# REF-IN-BLE-NS_4-2_Rigid.net
KiCad netlist of a schematic drawn in EAGLE
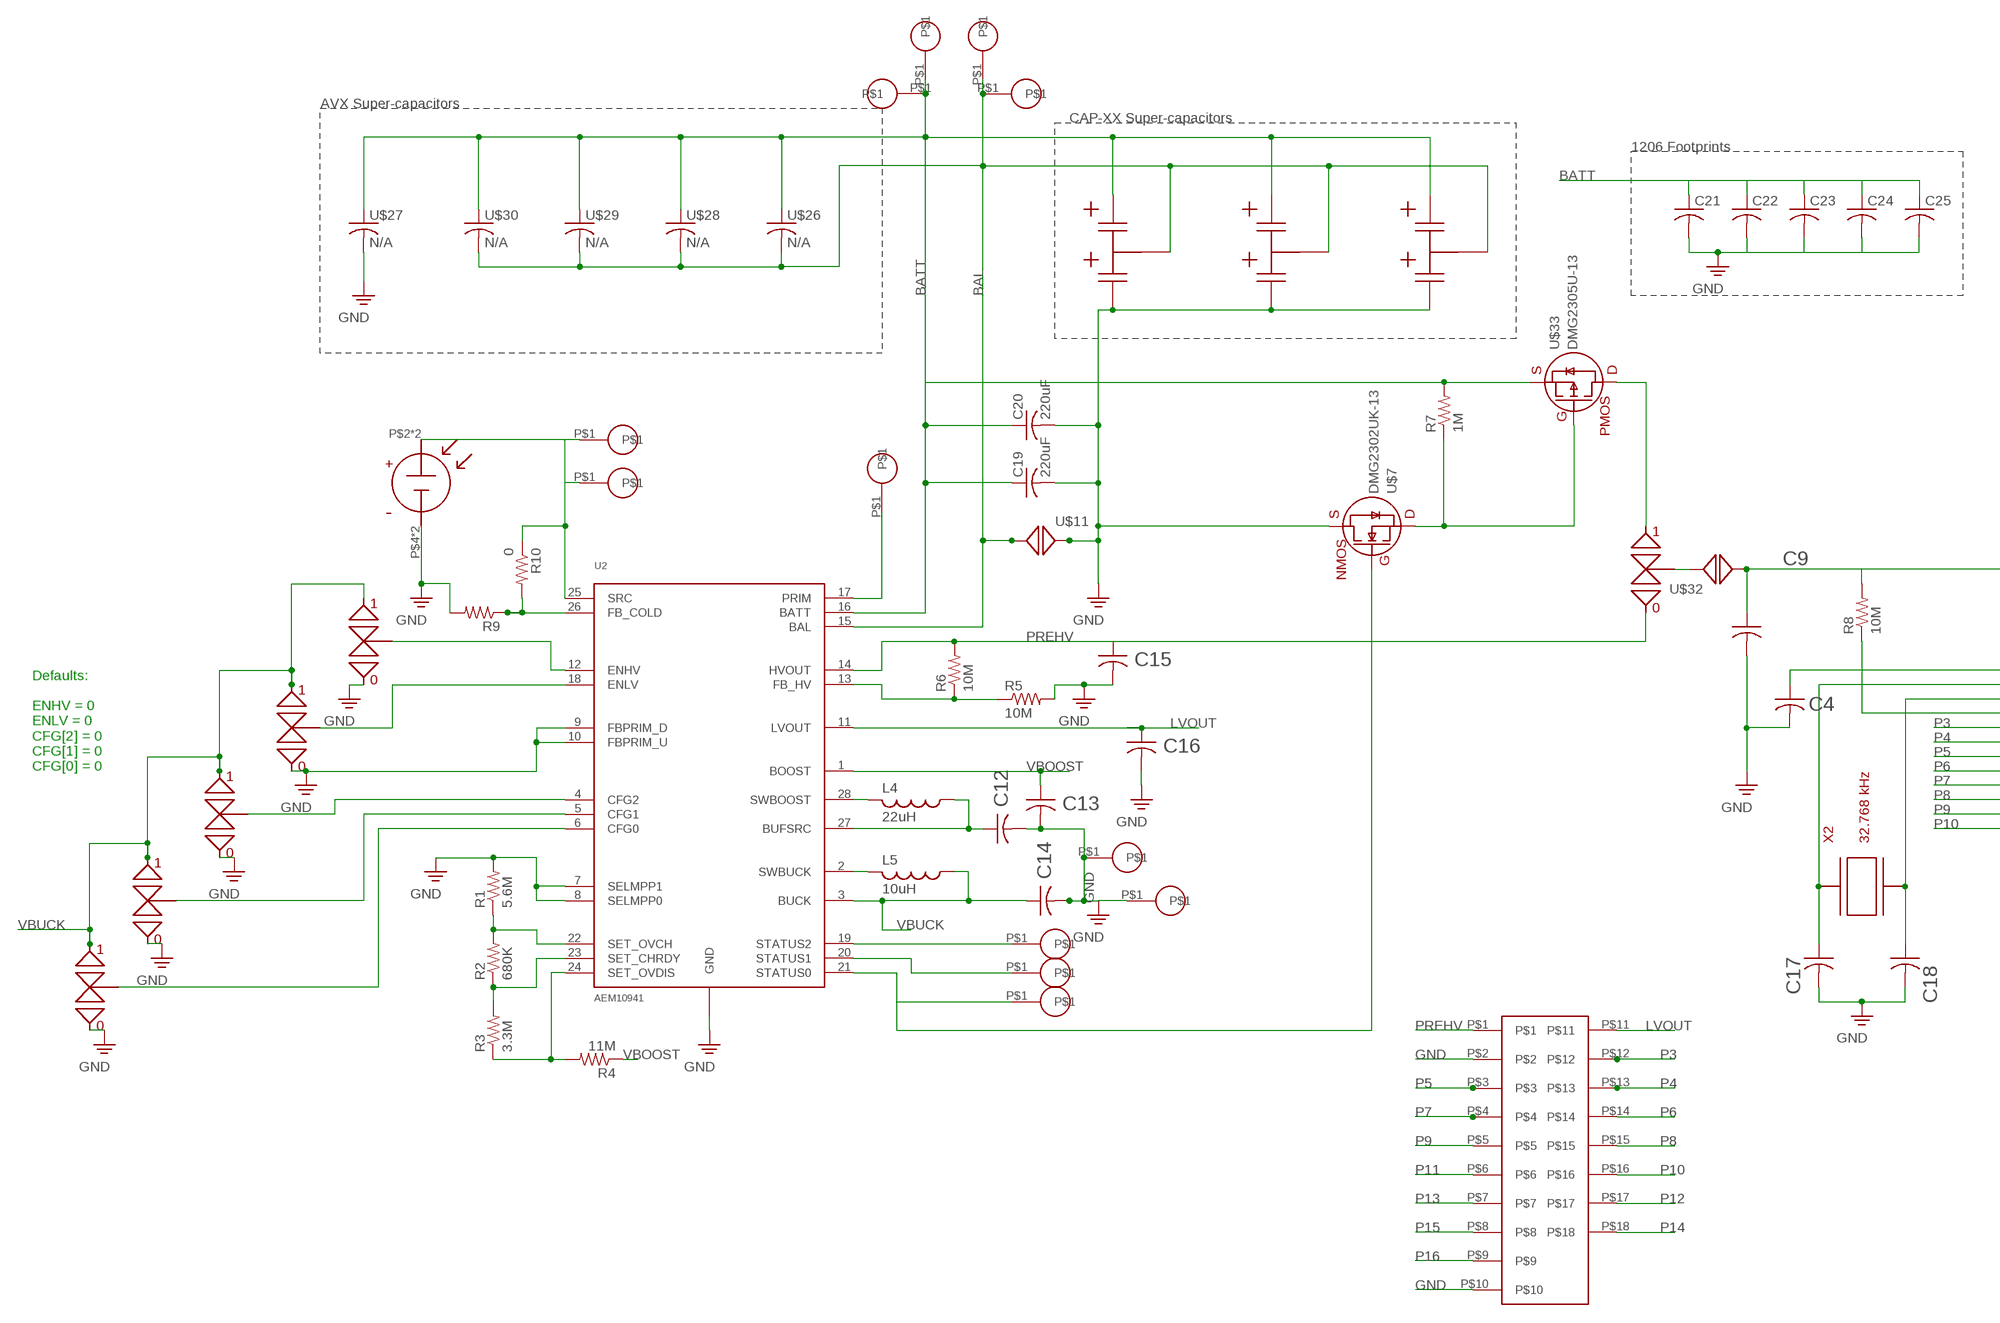
[diagram p0: schematic, sheet 1, part 1 of 2]
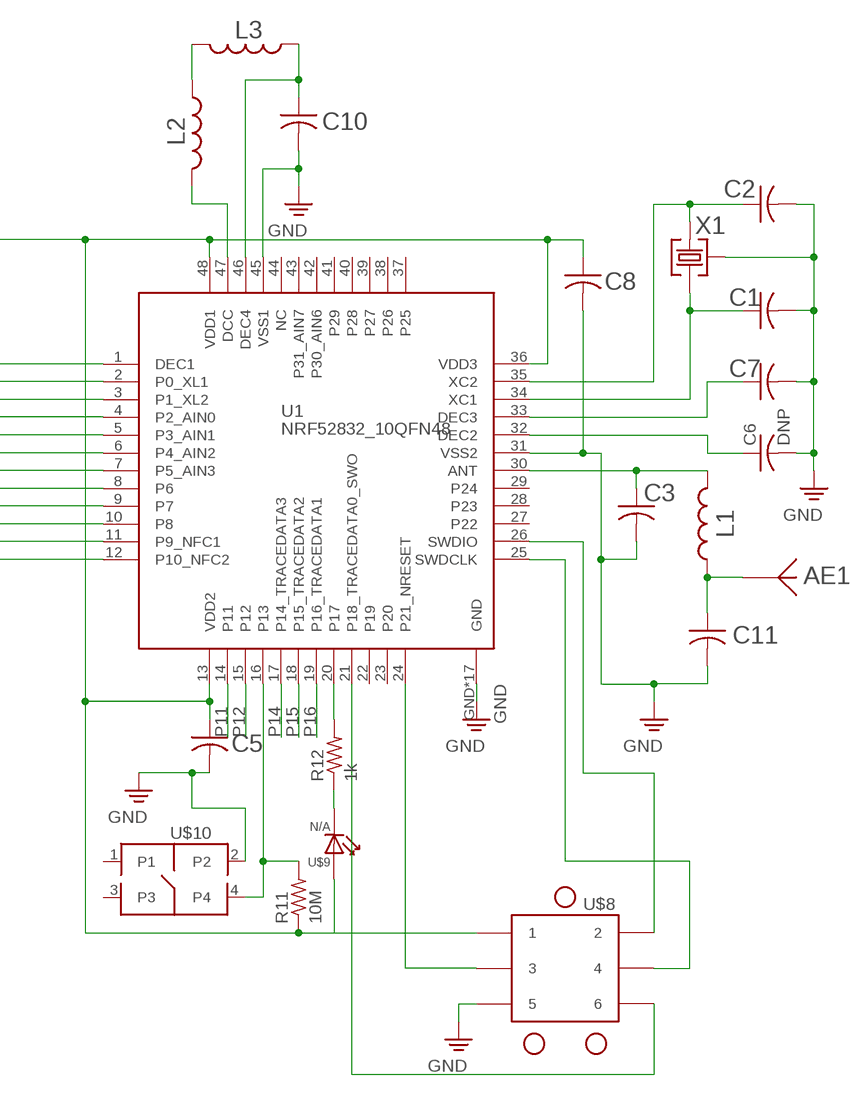
[diagram p1: schematic, sheet 1, part 2 of 2]

(export (version "E")
  (design (tool "Eeschema 10.0.6"))
  (components
    (comp (ref "AE1")
      (value "2.4GHZ_ANTENNAFLIPPED")
      (footprint "eagle-import:BLE_ANTENNA_NORDIC_FLIPPED")
      (libsource (lib "eagle-import") (part "2.4GHZ_ANTENNAFLIPPED"))
    )
    (comp (ref "C1")
      (value "12pF")
      (footprint "eagle-import:C0603")
      (fields (field (name "MFG_PART#") "C0603C120J5GACTU"))
      (libsource (lib "eagle-import") (part "C-USC0603T-12PF"))
    )
    (comp (ref "C2")
      (value "12pF")
      (footprint "eagle-import:C0603")
      (fields (field (name "MFG_PART#") "C0603C120J5GACTU"))
      (libsource (lib "eagle-import") (part "C-USC0603T-12PF"))
    )
    (comp (ref "C3")
      (value "0.8pF")
      (footprint "eagle-import:C0603")
      (fields (field (name "MFG_PART#") "CBR06C808B5GAC "))
      (libsource (lib "eagle-import") (part "C-USC0603T-0.8PF"))
    )
    (comp (ref "C4")
      (value "100nF")
      (footprint "eagle-import:C0603")
      (fields (field (name "MFG_PART#") "CL10B104KB8NNNC"))
      (libsource (lib "eagle-import") (part "C-USC0603T-100NF"))
    )
    (comp (ref "C5")
      (value "100nF")
      (footprint "eagle-import:C0603")
      (fields (field (name "MFG_PART#") "CL10B104KB8NNNC"))
      (libsource (lib "eagle-import") (part "C-USC0603T-100NF"))
    )
    (comp (ref "C6")
      (value "DNP")
      (footprint "eagle-import:C0603")
      (libsource (lib "eagle-import") (part "C-USC0603"))
    )
    (comp (ref "C7")
      (value "100pF")
      (footprint "eagle-import:C0603")
      (fields (field (name "MFG_PART#") "CL10C101JB8NNNC"))
      (libsource (lib "eagle-import") (part "C-USC0603T-100PF"))
    )
    (comp (ref "C8")
      (value "100nF")
      (footprint "eagle-import:C0603")
      (fields (field (name "MFG_PART#") "CL10B104KB8NNNC"))
      (libsource (lib "eagle-import") (part "C-USC0603T-100NF"))
    )
    (comp (ref "C9")
      (value "4.7uF")
      (footprint "eagle-import:C0603")
      (fields (field (name "MFG_PART#") "CL10A475KQ8NNWC "))
      (libsource (lib "eagle-import") (part "C-USC0603T-4.7UF"))
    )
    (comp (ref "C10")
      (value "1uF")
      (footprint "eagle-import:C0603")
      (fields (field (name "MFG_PART#") "CL10A105KP8NNNC ") (field (name "PERCENTAGE") "10%"))
      (libsource (lib "eagle-import") (part "C-USC0603T-1UF"))
    )
    (comp (ref "C11")
      (value "DNP")
      (footprint "eagle-import:C0603")
      (libsource (lib "eagle-import") (part "C-USC0603"))
    )
    (comp (ref "C12")
      (value "10uF")
      (footprint "eagle-import:C0603")
      (fields (field (name "MFG_PART#") "GRM188R61E106MA73D"))
      (libsource (lib "eagle-import") (part "C-USC0603T-10UF"))
    )
    (comp (ref "C13")
      (value "22uF")
      (footprint "eagle-import:C0603")
      (fields (field (name "MFG_PART#") "GRM188R61A226ME15D"))
      (libsource (lib "eagle-import") (part "C-USC0603T-22UF"))
    )
    (comp (ref "C14")
      (value "10uF")
      (footprint "eagle-import:C0603")
      (fields (field (name "MFG_PART#") "GRM188R61E106MA73D"))
      (libsource (lib "eagle-import") (part "C-USC0603T-10UF"))
    )
    (comp (ref "C15")
      (value "10uF")
      (footprint "eagle-import:C0603")
      (fields (field (name "MFG_PART#") "GRM188R61E106MA73D"))
      (libsource (lib "eagle-import") (part "C-USC0603T-10UF"))
    )
    (comp (ref "C16")
      (value "10uF")
      (footprint "eagle-import:C0603")
      (fields (field (name "MFG_PART#") "GRM188R61E106MA73D"))
      (libsource (lib "eagle-import") (part "C-USC0603T-10UF"))
    )
    (comp (ref "C17")
      (value "12p")
      (footprint "eagle-import:C0603")
      (fields (field (name "MFG_PART#") "C0603C120J5GACTU"))
      (libsource (lib "eagle-import") (part "C-USC0603T-12PF"))
    )
    (comp (ref "C18")
      (value "12p")
      (footprint "eagle-import:C0603")
      (fields (field (name "MFG_PART#") "C0603C120J5GACTU"))
      (libsource (lib "eagle-import") (part "C-USC0603T-12PF"))
    )
    (comp (ref "C19")
      (value "220uF")
      (footprint "eagle-import:C1206")
      (fields (field (name "MFG_PART#") "GRM31CC80G227ME11L"))
      (libsource (lib "eagle-import") (part "C-USC1206T-220UF"))
    )
    (comp (ref "C20")
      (value "220uF")
      (footprint "eagle-import:C1206")
      (fields (field (name "MFG_PART#") "GRM31CC80G227ME11L"))
      (libsource (lib "eagle-import") (part "C-USC1206T-220UF"))
    )
    (comp (ref "C21")
      (value "C-USC1206")
      (footprint "eagle-import:C1206")
      (libsource (lib "eagle-import") (part "C-USC1206"))
    )
    (comp (ref "C22")
      (value "C-USC1206")
      (footprint "eagle-import:C1206")
      (libsource (lib "eagle-import") (part "C-USC1206"))
    )
    (comp (ref "C23")
      (value "C-USC1206")
      (footprint "eagle-import:C1206")
      (libsource (lib "eagle-import") (part "C-USC1206"))
    )
    (comp (ref "C24")
      (value "C-USC1206")
      (footprint "eagle-import:C1206")
      (libsource (lib "eagle-import") (part "C-USC1206"))
    )
    (comp (ref "C25")
      (value "C-USC1206")
      (footprint "eagle-import:C1206")
      (libsource (lib "eagle-import") (part "C-USC1206"))
    )
    (comp (ref "L1")
      (value "3.9nH")
      (footprint "eagle-import:L0603")
      (fields (field (name "MFG_PART#") "L-14C3N9SV4T "))
      (libsource (lib "eagle-import") (part "L0603V-3.9NH"))
    )
    (comp (ref "L2")
      (value "10uH")
      (footprint "eagle-import:L0603")
      (fields (field (name "MFG_PART#") "LBR2012T100M"))
      (libsource (lib "eagle-import") (part "L0603V-10UH"))
    )
    (comp (ref "L3")
      (value "15nH")
      (footprint "eagle-import:L0603")
      (fields (field (name "MFG_PART#") "L-14C15NJV4T"))
      (libsource (lib "eagle-import") (part "L0603V-15NH"))
    )
    (comp (ref "L4")
      (value "22uH")
      (footprint "eagle-import:L1206")
      (libsource (lib "eagle-import") (part "L1206"))
    )
    (comp (ref "L5")
      (value "10uH")
      (footprint "eagle-import:L0603")
      (fields (field (name "MFG_PART#") "LBR2012T100M"))
      (libsource (lib "eagle-import") (part "L0603V-10UH"))
    )
    (comp (ref "R1")
      (value "5.6M")
      (footprint "eagle-import:R0603")
      (libsource (lib "eagle-import") (part "R-US_R0603"))
    )
    (comp (ref "R2")
      (value "680K")
      (footprint "eagle-import:R0603")
      (libsource (lib "eagle-import") (part "R-US_R0603"))
    )
    (comp (ref "R3")
      (value "3.3M")
      (footprint "eagle-import:R0603")
      (libsource (lib "eagle-import") (part "R-US_R0603"))
    )
    (comp (ref "R4")
      (value "11M")
      (footprint "eagle-import:R0603")
      (libsource (lib "eagle-import") (part "R-US_R0603"))
    )
    (comp (ref "R5")
      (value "10M")
      (footprint "eagle-import:R0603")
      (libsource (lib "eagle-import") (part "R-US_R0603"))
    )
    (comp (ref "R6")
      (value "10M")
      (footprint "eagle-import:R0603")
      (libsource (lib "eagle-import") (part "R-US_R0603"))
    )
    (comp (ref "R7")
      (value "1M")
      (footprint "eagle-import:R0603")
      (libsource (lib "eagle-import") (part "R-US_R0603"))
    )
    (comp (ref "R8")
      (value "10M")
      (footprint "eagle-import:R0603")
      (libsource (lib "eagle-import") (part "R-US_R0603"))
    )
    (comp (ref "R9")
      (value "R-US_R0603")
      (footprint "eagle-import:R0603")
      (libsource (lib "eagle-import") (part "R-US_R0603"))
    )
    (comp (ref "R10")
      (value "0")
      (footprint "eagle-import:R0603")
      (libsource (lib "eagle-import") (part "R-US_R0603"))
    )
    (comp (ref "R11")
      (value "10M")
      (footprint "eagle-import:R0603")
      (libsource (lib "eagle-import") (part "R-US_R0603"))
    )
    (comp (ref "R12")
      (value "1k")
      (footprint "eagle-import:R0603")
      (libsource (lib "eagle-import") (part "R-US_R0603"))
    )
    (comp (ref "U$2")
      (value "N/A")
      (footprint "eagle-import:DOUBLE_SOLDER_BRIDGE_0_CLOSED")
      (libsource (lib "eagle-import") (part "DOUBLE_SOLDER_BRIDGE0_CLOSED"))
    )
    (comp (ref "U$3")
      (value "N/A")
      (footprint "eagle-import:DOUBLE_SOLDER_BRIDGE_0_CLOSED")
      (libsource (lib "eagle-import") (part "DOUBLE_SOLDER_BRIDGE0_CLOSED"))
    )
    (comp (ref "U$4")
      (value "N/A")
      (footprint "eagle-import:DOUBLE_SOLDER_BRIDGE_0_CLOSED")
      (libsource (lib "eagle-import") (part "DOUBLE_SOLDER_BRIDGE0_CLOSED"))
    )
    (comp (ref "U$5")
      (value "N/A")
      (footprint "eagle-import:DOUBLE_SOLDER_BRIDGE_0_CLOSED")
      (libsource (lib "eagle-import") (part "DOUBLE_SOLDER_BRIDGE0_CLOSED"))
    )
    (comp (ref "U$6")
      (value "N/A")
      (footprint "eagle-import:DOUBLE_SOLDER_BRIDGE_0_CLOSED")
      (libsource (lib "eagle-import") (part "DOUBLE_SOLDER_BRIDGE0_CLOSED"))
    )
    (comp (ref "U$7")
      (value "DMG2302UK-13")
      (footprint "eagle-import:SOT-23-3-DIODESINC")
      (libsource (lib "eagle-import") (part "DMG2302UK-13"))
    )
    (comp (ref "U$8")
      (value "N/A")
      (footprint "eagle-import:TC2030-IDC")
      (libsource (lib "eagle-import") (part "TC2030-IDC"))
    )
    (comp (ref "U$9")
      (value "N/A")
      (footprint "eagle-import:APT1608LZGCK")
      (fields (field (name "MFG_PART#") "APT1608LZGCK"))
      (libsource (lib "eagle-import") (part "APT1608LZGCK"))
    )
    (comp (ref "U$10")
      (value "MJTP1140")
      (footprint "eagle-import:MJTP1140A")
      (fields (field (name "MFG_PART#") "TL3315NF100Q "))
      (libsource (lib "eagle-import") (part "MJTP1140"))
    )
    (comp (ref "U$11")
      (value "SOLDER_BRIGDECLOSED")
      (footprint "eagle-import:SOLDER_BRIDGE_CLOSED")
      (libsource (lib "eagle-import") (part "SOLDER_BRIGDECLOSED"))
    )
    (comp (ref "U$12")
      (value "N/A")
      (footprint "eagle-import:1MM_PAD")
      (libsource (lib "eagle-import") (part "1MM_PAD"))
    )
    (comp (ref "U$13")
      (value "N/A")
      (footprint "eagle-import:1MM_PAD")
      (libsource (lib "eagle-import") (part "1MM_PAD"))
    )
    (comp (ref "U$14")
      (value "N/A")
      (footprint "eagle-import:1MM_PAD")
      (libsource (lib "eagle-import") (part "1MM_PAD"))
    )
    (comp (ref "U$15")
      (value "N/A")
      (footprint "eagle-import:1MM_PAD")
      (libsource (lib "eagle-import") (part "1MM_PAD"))
    )
    (comp (ref "U$16")
      (value "SOLAR_CELL_LL200-2.4-37")
      (footprint "eagle-import:SOLAR_CELL_37X54MM")
      (libsource (lib "eagle-import") (part "SOLAR_CELL_LL200-2.4-37"))
    )
    (comp (ref "U$17")
      (value "N/A")
      (footprint "eagle-import:1MM_PAD")
      (libsource (lib "eagle-import") (part "1MM_PAD"))
    )
    (comp (ref "U$18")
      (value "N/A")
      (footprint "eagle-import:1MM_PAD")
      (libsource (lib "eagle-import") (part "1MM_PAD"))
    )
    (comp (ref "U$19")
      (value "N/A")
      (footprint "eagle-import:1MM_PAD")
      (libsource (lib "eagle-import") (part "1MM_PAD"))
    )
    (comp (ref "U$20")
      (value "18PIN_CONN")
      (footprint "eagle-import:20PIN_CONN")
      (libsource (lib "eagle-import") (part "18PIN_CONN"))
    )
    (comp (ref "U$23")
      (value "N/A")
      (footprint "eagle-import:CAP-XX_A-TYPE")
      (libsource (lib "eagle-import") (part "CAP-XX_A-TYPE"))
    )
    (comp (ref "U$24")
      (value "N/A")
      (footprint "eagle-import:CAP-XX_S-TYPE")
      (libsource (lib "eagle-import") (part "CAP-XX_S-TYPE"))
    )
    (comp (ref "U$25")
      (value "N/A")
      (footprint "eagle-import:CAP-XX_W-TYPE")
      (libsource (lib "eagle-import") (part "CAP-XX_W-TYPE"))
    )
    (comp (ref "U$26")
      (value "N/A")
      (footprint "eagle-import:BZ01_L-TYPE")
      (libsource (lib "eagle-import") (part "BZ01_L-TYPE"))
    )
    (comp (ref "U$27")
      (value "N/A")
      (footprint "eagle-import:BZ059_N-TYPE")
      (libsource (lib "eagle-import") (part "BZ059_N-TYPE"))
    )
    (comp (ref "U$28")
      (value "N/A")
      (footprint "eagle-import:BZ01_S-TYPE")
      (libsource (lib "eagle-import") (part "BZ01_S-TYPE"))
    )
    (comp (ref "U$29")
      (value "N/A")
      (footprint "eagle-import:BZ05_S-TYPE")
      (libsource (lib "eagle-import") (part "BZ05_S-TYPE"))
    )
    (comp (ref "U$30")
      (value "N/A")
      (footprint "eagle-import:BZ09_S-TYPE")
      (libsource (lib "eagle-import") (part "BZ09_S-TYPE"))
    )
    (comp (ref "U$31")
      (value "DOUBLE_SOLDER_BRIDGE1_CLOSED")
      (footprint "eagle-import:DOUBLE_SOLDER_BRIDGE_1_CLOSED")
      (libsource (lib "eagle-import") (part "DOUBLE_SOLDER_BRIDGE1_CLOSED"))
    )
    (comp (ref "U$32")
      (value "SOLDER_BRIGDECLOSED")
      (footprint "eagle-import:SOLDER_BRIDGE_CLOSED")
      (libsource (lib "eagle-import") (part "SOLDER_BRIGDECLOSED"))
    )
    (comp (ref "U$33")
      (value "DMG2305U-13")
      (footprint "eagle-import:SOT-23-3-DIODESINC")
      (libsource (lib "eagle-import") (part "DMG2305U-13"))
    )
    (comp (ref "U$35")
      (value "N/A")
      (footprint "eagle-import:1MM_PAD")
      (libsource (lib "eagle-import") (part "1MM_PAD"))
    )
    (comp (ref "U$36")
      (value "N/A")
      (footprint "eagle-import:1MM_PAD")
      (libsource (lib "eagle-import") (part "1MM_PAD"))
    )
    (comp (ref "U$39")
      (value "N/A")
      (footprint "eagle-import:1MM_PAD")
      (libsource (lib "eagle-import") (part "1MM_PAD"))
    )
    (comp (ref "U$40")
      (value "N/A")
      (footprint "eagle-import:1MM_PAD")
      (libsource (lib "eagle-import") (part "1MM_PAD"))
    )
    (comp (ref "U$41")
      (value "N/A")
      (footprint "eagle-import:1MM_PAD")
      (libsource (lib "eagle-import") (part "1MM_PAD"))
    )
    (comp (ref "U1")
      (value "NRF52832_10QFN48")
      (footprint "eagle-import:NRF52832_10")
      (fields (field (name "MFG_PART#") "NRF52832-QFAA-R"))
      (libsource (lib "eagle-import") (part "NRF52832_10QFN48"))
    )
    (comp (ref "U2")
      (value "AEM10941")
      (footprint "eagle-import:QFN28_5X5_05PITCH")
      (fields (field (name "MFG_PART#") "AEM10941-QFN "))
      (libsource (lib "eagle-import") (part "AEM10941"))
    )
    (comp (ref "X1")
      (value "32 MHz")
      (footprint "eagle-import:FA-128-EPSON")
      (fields (field (name "MFG_PART#") "FA-128 32.0000MF10Z-AJ3"))
      (libsource (lib "eagle-import") (part "FA-128-32MHZMF10Z-AJ5"))
    )
    (comp (ref "X2")
      (value "32.768 kHz")
      (footprint "eagle-import:FC-135")
      (fields (field (name "MFG_PART#") "FC-135 32.7680KA-AC"))
      (libsource (lib "eagle-import") (part "FC-135_32.7680KA-AC"))
    )
  )
  (nets
    (net (code "1") (name "/BAL") (class "Default")
      (node (ref "U$11") (pin "P$1") (pinfunction "P1_P$1") (pintype "bidirectional"))
      (node (ref "U$19") (pin "P$1") (pinfunction "P$1_P$1") (pintype "bidirectional"))
      (node (ref "U$23") (pin "P$1") (pinfunction "BAL_P$1") (pintype "bidirectional"))
      (node (ref "U$24") (pin "P$1") (pinfunction "BAL_P$1") (pintype "bidirectional"))
      (node (ref "U$25") (pin "P$1") (pinfunction "BAL_P$1") (pintype "bidirectional"))
      (node (ref "U$26") (pin "P$3") (pinfunction "2_P$3") (pintype "passive"))
      (node (ref "U$26") (pin "P$4") (pinfunction "2_P$4") (pintype "passive"))
      (node (ref "U$28") (pin "P$3") (pinfunction "2_P$3") (pintype "passive"))
      (node (ref "U$29") (pin "P$3") (pinfunction "2_P$3") (pintype "passive"))
      (node (ref "U$30") (pin "P$3") (pinfunction "2_P$3") (pintype "passive"))
      (node (ref "U$41") (pin "P$1") (pinfunction "P$1_P$1") (pintype "bidirectional"))
      (node (ref "U2") (pin "15") (pinfunction "BAL_15") (pintype "bidirectional"))
    )
    (net (code "2") (name "/BATT") (class "Default")
      (node (ref "C19") (pin "1") (pinfunction "1_1") (pintype "passive"))
      (node (ref "C20") (pin "1") (pinfunction "1_1") (pintype "passive"))
      (node (ref "C21") (pin "1") (pinfunction "1_1") (pintype "passive"))
      (node (ref "C22") (pin "1") (pinfunction "1_1") (pintype "passive"))
      (node (ref "C23") (pin "1") (pinfunction "1_1") (pintype "passive"))
      (node (ref "C24") (pin "1") (pinfunction "1_1") (pintype "passive"))
      (node (ref "C25") (pin "1") (pinfunction "1_1") (pintype "passive"))
      (node (ref "R7") (pin "2") (pinfunction "2_2") (pintype "passive"))
      (node (ref "U$18") (pin "P$1") (pinfunction "P$1_P$1") (pintype "bidirectional"))
      (node (ref "U$23") (pin "P$2") (pinfunction "+_P$2") (pintype "bidirectional"))
      (node (ref "U$24") (pin "P$2") (pinfunction "+_P$2") (pintype "bidirectional"))
      (node (ref "U$25") (pin "P$2") (pinfunction "+_P$2") (pintype "bidirectional"))
      (node (ref "U$26") (pin "P$1") (pinfunction "1_P$1") (pintype "passive"))
      (node (ref "U$26") (pin "P$2") (pinfunction "1_P$2") (pintype "passive"))
      (node (ref "U$27") (pin "P$1") (pinfunction "1_P$1") (pintype "passive"))
      (node (ref "U$28") (pin "P$1") (pinfunction "1_P$1") (pintype "passive"))
      (node (ref "U$28") (pin "P$2") (pinfunction "1_P$2") (pintype "passive"))
      (node (ref "U$29") (pin "P$1") (pinfunction "1_P$1") (pintype "passive"))
      (node (ref "U$29") (pin "P$2") (pinfunction "1_P$2") (pintype "passive"))
      (node (ref "U$30") (pin "P$1") (pinfunction "1_P$1") (pintype "passive"))
      (node (ref "U$30") (pin "P$2") (pinfunction "1_P$2") (pintype "passive"))
      (node (ref "U$33") (pin "2") (pinfunction "S_2") (pintype "bidirectional"))
      (node (ref "U$40") (pin "P$1") (pinfunction "P$1_P$1") (pintype "bidirectional"))
      (node (ref "U2") (pin "16") (pinfunction "BATT_16") (pintype "bidirectional"))
    )
    (net (code "3") (name "/LVOUT") (class "Default")
      (node (ref "C16") (pin "1") (pinfunction "1_1") (pintype "passive"))
      (node (ref "U$20") (pin "P$11") (pinfunction "P$11_P$11") (pintype "bidirectional"))
      (node (ref "U2") (pin "11") (pinfunction "LVOUT_11") (pintype "output"))
    )
    (net (code "4") (name "/P3") (class "Default")
      (node (ref "U$20") (pin "P$12") (pinfunction "P$12_P$12") (pintype "bidirectional"))
      (node (ref "U1") (pin "5") (pinfunction "P3_AIN1_5") (pintype "bidirectional"))
    )
    (net (code "5") (name "/P4") (class "Default")
      (node (ref "U$20") (pin "P$13") (pinfunction "P$13_P$13") (pintype "bidirectional"))
      (node (ref "U1") (pin "6") (pinfunction "P4_AIN2_6") (pintype "bidirectional"))
    )
    (net (code "6") (name "/P5") (class "Default")
      (node (ref "U$20") (pin "P$3") (pinfunction "P$3_P$3") (pintype "bidirectional"))
      (node (ref "U1") (pin "7") (pinfunction "P5_AIN3_7") (pintype "bidirectional"))
    )
    (net (code "7") (name "/P6") (class "Default")
      (node (ref "U$20") (pin "P$14") (pinfunction "P$14_P$14") (pintype "bidirectional"))
      (node (ref "U1") (pin "8") (pinfunction "P6_8") (pintype "bidirectional"))
    )
    (net (code "8") (name "/P7") (class "Default")
      (node (ref "U$20") (pin "P$4") (pinfunction "P$4_P$4") (pintype "bidirectional"))
      (node (ref "U1") (pin "9") (pinfunction "P7_9") (pintype "bidirectional"))
    )
    (net (code "9") (name "/P8") (class "Default")
      (node (ref "U$20") (pin "P$15") (pinfunction "P$15_P$15") (pintype "bidirectional"))
      (node (ref "U1") (pin "10") (pinfunction "P8_10") (pintype "bidirectional"))
    )
    (net (code "10") (name "/P9") (class "Default")
      (node (ref "U$20") (pin "P$5") (pinfunction "P$5_P$5") (pintype "bidirectional"))
      (node (ref "U1") (pin "11") (pinfunction "P9_NFC1_11") (pintype "bidirectional"))
    )
    (net (code "11") (name "/P10") (class "Default")
      (node (ref "U$20") (pin "P$16") (pinfunction "P$16_P$16") (pintype "bidirectional"))
      (node (ref "U1") (pin "12") (pinfunction "P10_NFC2_12") (pintype "bidirectional"))
    )
    (net (code "12") (name "/P11") (class "Default")
      (node (ref "U$20") (pin "P$6") (pinfunction "P$6_P$6") (pintype "bidirectional"))
      (node (ref "U1") (pin "14") (pinfunction "P11_14") (pintype "bidirectional"))
    )
    (net (code "13") (name "/P12") (class "Default")
      (node (ref "U$20") (pin "P$17") (pinfunction "P$17_P$17") (pintype "bidirectional"))
      (node (ref "U1") (pin "15") (pinfunction "P12_15") (pintype "bidirectional"))
    )
    (net (code "14") (name "/P13") (class "Default")
      (node (ref "U$20") (pin "P$7") (pinfunction "P$7_P$7") (pintype "bidirectional"))
    )
    (net (code "15") (name "/P14") (class "Default")
      (node (ref "U$20") (pin "P$18") (pinfunction "P$18_P$18") (pintype "bidirectional"))
      (node (ref "U1") (pin "17") (pinfunction "P14_TRACEDATA3_17") (pintype "bidirectional"))
    )
    (net (code "16") (name "/P15") (class "Default")
      (node (ref "U$20") (pin "P$8") (pinfunction "P$8_P$8") (pintype "bidirectional"))
      (node (ref "U1") (pin "18") (pinfunction "P15_TRACEDATA2_18") (pintype "bidirectional"))
    )
    (net (code "17") (name "/P16") (class "Default")
      (node (ref "U$20") (pin "P$9") (pinfunction "P$9_P$9") (pintype "bidirectional"))
      (node (ref "U1") (pin "19") (pinfunction "P16_TRACEDATA1_19") (pintype "bidirectional"))
    )
    (net (code "18") (name "/PREHV") (class "Default")
      (node (ref "C15") (pin "1") (pinfunction "1_1") (pintype "passive"))
      (node (ref "R6") (pin "2") (pinfunction "2_2") (pintype "passive"))
      (node (ref "U$20") (pin "P$1") (pinfunction "P$1_P$1") (pintype "bidirectional"))
      (node (ref "U$31") (pin "IN0") (pinfunction "IN0_IN0") (pintype "bidirectional"))
      (node (ref "U2") (pin "14") (pinfunction "HVOUT_14") (pintype "output"))
    )
    (net (code "19") (name "/VBOOST") (class "Default")
      (node (ref "C13") (pin "1") (pinfunction "1_1") (pintype "passive"))
      (node (ref "R4") (pin "1") (pinfunction "1_1") (pintype "passive"))
      (node (ref "U2") (pin "1") (pinfunction "BOOST_1") (pintype "bidirectional"))
    )
    (net (code "20") (name "/VBUCK") (class "Default")
      (node (ref "C14") (pin "1") (pinfunction "1_1") (pintype "passive"))
      (node (ref "L5") (pin "1") (pinfunction "1_1") (pintype "passive"))
      (node (ref "U$2") (pin "IN1") (pinfunction "IN1_IN1") (pintype "bidirectional"))
      (node (ref "U$3") (pin "IN1") (pinfunction "IN1_IN1") (pintype "bidirectional"))
      (node (ref "U$4") (pin "IN1") (pinfunction "IN1_IN1") (pintype "bidirectional"))
      (node (ref "U$5") (pin "IN1") (pinfunction "IN1_IN1") (pintype "bidirectional"))
      (node (ref "U$6") (pin "IN1") (pinfunction "IN1_IN1") (pintype "bidirectional"))
      (node (ref "U2") (pin "3") (pinfunction "BUCK_3") (pintype "bidirectional"))
    )
    (net (code "21") (name "GND") (class "Default")
      (node (ref "C1") (pin "2") (pinfunction "2_2") (pintype "passive"))
      (node (ref "C10") (pin "2") (pinfunction "2_2") (pintype "passive"))
      (node (ref "C11") (pin "2") (pinfunction "2_2") (pintype "passive"))
      (node (ref "C12") (pin "2") (pinfunction "2_2") (pintype "passive"))
      (node (ref "C13") (pin "2") (pinfunction "2_2") (pintype "passive"))
      (node (ref "C14") (pin "2") (pinfunction "2_2") (pintype "passive"))
      (node (ref "C15") (pin "2") (pinfunction "2_2") (pintype "passive"))
      (node (ref "C16") (pin "2") (pinfunction "2_2") (pintype "passive"))
      (node (ref "C17") (pin "2") (pinfunction "2_2") (pintype "passive"))
      (node (ref "C18") (pin "2") (pinfunction "2_2") (pintype "passive"))
      (node (ref "C19") (pin "2") (pinfunction "2_2") (pintype "passive"))
      (node (ref "C2") (pin "2") (pinfunction "2_2") (pintype "passive"))
      (node (ref "C20") (pin "2") (pinfunction "2_2") (pintype "passive"))
      (node (ref "C21") (pin "2") (pinfunction "2_2") (pintype "passive"))
      (node (ref "C22") (pin "2") (pinfunction "2_2") (pintype "passive"))
      (node (ref "C23") (pin "2") (pinfunction "2_2") (pintype "passive"))
      (node (ref "C24") (pin "2") (pinfunction "2_2") (pintype "passive"))
      (node (ref "C25") (pin "2") (pinfunction "2_2") (pintype "passive"))
      (node (ref "C3") (pin "2") (pinfunction "2_2") (pintype "passive"))
      (node (ref "C4") (pin "2") (pinfunction "2_2") (pintype "passive"))
      (node (ref "C5") (pin "2") (pinfunction "2_2") (pintype "passive"))
      (node (ref "C6") (pin "2") (pinfunction "2_2") (pintype "passive"))
      (node (ref "C7") (pin "2") (pinfunction "2_2") (pintype "passive"))
      (node (ref "C8") (pin "2") (pinfunction "2_2") (pintype "passive"))
      (node (ref "C9") (pin "2") (pinfunction "2_2") (pintype "passive"))
      (node (ref "R1") (pin "2") (pinfunction "2_2") (pintype "passive"))
      (node (ref "R5") (pin "2") (pinfunction "2_2") (pintype "passive"))
      (node (ref "R9") (pin "2") (pinfunction "2_2") (pintype "passive"))
      (node (ref "U$10") (pin "2") (pinfunction "P2_2") (pintype "bidirectional"))
      (node (ref "U$11") (pin "P$2") (pinfunction "P2_P$2") (pintype "bidirectional"))
      (node (ref "U$16") (pin "P$4") (pinfunction "GND_P$4") (pintype "bidirectional"))
      (node (ref "U$16") (pin "P$5") (pinfunction "GND_P$5") (pintype "bidirectional"))
      (node (ref "U$17") (pin "P$1") (pinfunction "P$1_P$1") (pintype "bidirectional"))
      (node (ref "U$2") (pin "IN0") (pinfunction "IN0_IN0") (pintype "bidirectional"))
      (node (ref "U$20") (pin "P$10") (pinfunction "P$10_P$10") (pintype "bidirectional"))
      (node (ref "U$20") (pin "P$2") (pinfunction "P$2_P$2") (pintype "bidirectional"))
      (node (ref "U$23") (pin "P$3") (pinfunction "-_P$3") (pintype "bidirectional"))
      (node (ref "U$24") (pin "P$3") (pinfunction "-_P$3") (pintype "bidirectional"))
      (node (ref "U$25") (pin "P$3") (pinfunction "-_P$3") (pintype "bidirectional"))
      (node (ref "U$27") (pin "P$2") (pinfunction "2_P$2") (pintype "passive"))
      (node (ref "U$3") (pin "IN0") (pinfunction "IN0_IN0") (pintype "bidirectional"))
      (node (ref "U$35") (pin "P$1") (pinfunction "P$1_P$1") (pintype "bidirectional"))
      (node (ref "U$4") (pin "IN0") (pinfunction "IN0_IN0") (pintype "bidirectional"))
      (node (ref "U$5") (pin "IN0") (pinfunction "IN0_IN0") (pintype "bidirectional"))
      (node (ref "U$6") (pin "IN0") (pinfunction "IN0_IN0") (pintype "bidirectional"))
      (node (ref "U$7") (pin "2") (pinfunction "S_2") (pintype "bidirectional"))
      (node (ref "U$8") (pin "P5") (pinfunction "5_P5") (pintype "bidirectional"))
      (node (ref "U1") (pin "31") (pinfunction "VSS2_31") (pintype "bidirectional"))
      (node (ref "U1") (pin "45") (pinfunction "VSS1_45") (pintype "bidirectional"))
      (node (ref "U1") (pin "GND") (pinfunction "GND_GND") (pintype "bidirectional"))
      (node (ref "U1") (pin "P$10") (pinfunction "GND_P$10") (pintype "bidirectional"))
      (node (ref "U1") (pin "P$11") (pinfunction "GND_P$11") (pintype "bidirectional"))
      (node (ref "U1") (pin "P$12") (pinfunction "GND_P$12") (pintype "bidirectional"))
      (node (ref "U1") (pin "P$13") (pinfunction "GND_P$13") (pintype "bidirectional"))
      (node (ref "U1") (pin "P$14") (pinfunction "GND_P$14") (pintype "bidirectional"))
      (node (ref "U1") (pin "P$15") (pinfunction "GND_P$15") (pintype "bidirectional"))
      (node (ref "U1") (pin "P$16") (pinfunction "GND_P$16") (pintype "bidirectional"))
      (node (ref "U1") (pin "P$17") (pinfunction "GND_P$17") (pintype "bidirectional"))
      (node (ref "U1") (pin "P$2") (pinfunction "GND_P$2") (pintype "bidirectional"))
      (node (ref "U1") (pin "P$3") (pinfunction "GND_P$3") (pintype "bidirectional"))
      (node (ref "U1") (pin "P$4") (pinfunction "GND_P$4") (pintype "bidirectional"))
      (node (ref "U1") (pin "P$5") (pinfunction "GND_P$5") (pintype "bidirectional"))
      (node (ref "U1") (pin "P$6") (pinfunction "GND_P$6") (pintype "bidirectional"))
      (node (ref "U1") (pin "P$7") (pinfunction "GND_P$7") (pintype "bidirectional"))
      (node (ref "U1") (pin "P$8") (pinfunction "GND_P$8") (pintype "bidirectional"))
      (node (ref "U1") (pin "P$9") (pinfunction "GND_P$9") (pintype "bidirectional"))
      (node (ref "U2") (pin "10") (pinfunction "FBPRIM_U_10") (pintype "bidirectional"))
      (node (ref "U2") (pin "7") (pinfunction "SELMPP1_7") (pintype "input"))
      (node (ref "U2") (pin "8") (pinfunction "SELMPP0_8") (pintype "input"))
      (node (ref "U2") (pin "9") (pinfunction "FBPRIM_D_9") (pintype "bidirectional"))
      (node (ref "U2") (pin "GND") (pinfunction "GND_GND") (pintype "power_in"))
      (node (ref "U2") (pin "GND1") (pinfunction "GND_GND1") (pintype "power_in"))
      (node (ref "U2") (pin "GND2") (pinfunction "GND_GND2") (pintype "power_in"))
      (node (ref "U2") (pin "GND3") (pinfunction "GND_GND3") (pintype "power_in"))
      (node (ref "U2") (pin "GND4") (pinfunction "GND_GND4") (pintype "power_in"))
      (node (ref "U2") (pin "GND5") (pinfunction "GND_GND5") (pintype "power_in"))
      (node (ref "X1") (pin "P2") (pinfunction "P3_P2") (pintype "bidirectional"))
      (node (ref "X1") (pin "P4") (pinfunction "P3_P4") (pintype "bidirectional"))
    )
    (net (code "22") (name "Net-(AE1-PadP$1)") (class "Default")
      (node (ref "AE1") (pin "P$1") (pinfunction "P$1_P$1") (pintype "bidirectional"))
      (node (ref "C11") (pin "1") (pinfunction "1_1") (pintype "passive"))
      (node (ref "L1") (pin "1") (pinfunction "1_1") (pintype "passive"))
    )
    (net (code "23") (name "Net-(L2-Pad1)") (class "Default")
      (node (ref "L2") (pin "1") (pinfunction "1_1") (pintype "passive"))
      (node (ref "L3") (pin "2") (pinfunction "2_2") (pintype "passive"))
    )
    (net (code "24") (name "Net-(L4-1)") (class "Default")
      (node (ref "C12") (pin "1") (pinfunction "1_1") (pintype "passive"))
      (node (ref "L4") (pin "P$1") (pinfunction "1_P$1") (pintype "passive"))
      (node (ref "U2") (pin "27") (pinfunction "BUFSRC_27") (pintype "bidirectional"))
    )
    (net (code "25") (name "Net-(L4-2)") (class "Default")
      (node (ref "L4") (pin "P$2") (pinfunction "2_P$2") (pintype "passive"))
      (node (ref "U2") (pin "28") (pinfunction "SWBOOST_28") (pintype "bidirectional"))
    )
    (net (code "26") (name "Net-(R12-Pad1)") (class "Default")
      (node (ref "R12") (pin "1") (pinfunction "1_1") (pintype "passive"))
      (node (ref "U$9") (pin "C") (pinfunction "C_C") (pintype "bidirectional"))
    )
    (net (code "27") (name "Net-(U$7-G)") (class "Default")
      (node (ref "U$15") (pin "P$1") (pinfunction "P$1_P$1") (pintype "bidirectional"))
      (node (ref "U$7") (pin "1") (pinfunction "G_1") (pintype "bidirectional"))
      (node (ref "U2") (pin "21") (pinfunction "STATUS0_21") (pintype "output"))
    )
    (net (code "28") (name "Net-(U$8-2)") (class "Default")
      (node (ref "U$8") (pin "P2") (pinfunction "2_P2") (pintype "bidirectional"))
      (node (ref "U1") (pin "26") (pinfunction "SWDIO_26") (pintype "bidirectional"))
    )
    (net (code "29") (name "Net-(U$8-3)") (class "Default")
      (node (ref "U$8") (pin "P3") (pinfunction "3_P3") (pintype "bidirectional"))
      (node (ref "U1") (pin "24") (pinfunction "P21_NRESET_24") (pintype "bidirectional"))
    )
    (net (code "30") (name "Net-(U$8-4)") (class "Default")
      (node (ref "U$8") (pin "P4") (pinfunction "4_P4") (pintype "bidirectional"))
      (node (ref "U1") (pin "25") (pinfunction "SWDCLK_25") (pintype "bidirectional"))
    )
    (net (code "31") (name "Net-(U$8-6)") (class "Default")
      (node (ref "U$8") (pin "P6") (pinfunction "6_P6") (pintype "bidirectional"))
      (node (ref "U1") (pin "21") (pinfunction "P18_TRACEDATA0_SWO_21") (pintype "bidirectional"))
    )
    (net (code "32") (name "Net-(U$10-P4)") (class "Default")
      (node (ref "R11") (pin "2") (pinfunction "2_2") (pintype "passive"))
      (node (ref "U$10") (pin "4") (pinfunction "P4_4") (pintype "bidirectional"))
      (node (ref "U1") (pin "16") (pinfunction "P13_16") (pintype "bidirectional"))
    )
    (net (code "33") (name "Net-(U$32-P1)") (class "Default")
      (node (ref "C5") (pin "1") (pinfunction "1_1") (pintype "passive"))
      (node (ref "C8") (pin "1") (pinfunction "1_1") (pintype "passive"))
      (node (ref "C9") (pin "1") (pinfunction "1_1") (pintype "passive"))
      (node (ref "R11") (pin "1") (pinfunction "1_1") (pintype "passive"))
      (node (ref "R8") (pin "2") (pinfunction "2_2") (pintype "passive"))
      (node (ref "U$32") (pin "P$1") (pinfunction "P1_P$1") (pintype "bidirectional"))
      (node (ref "U$8") (pin "P1") (pinfunction "1_P1") (pintype "bidirectional"))
      (node (ref "U$9") (pin "A") (pinfunction "A_A") (pintype "bidirectional"))
      (node (ref "U1") (pin "13") (pinfunction "VDD2_13") (pintype "bidirectional"))
      (node (ref "U1") (pin "36") (pinfunction "VDD3_36") (pintype "bidirectional"))
      (node (ref "U1") (pin "48") (pinfunction "VDD1_48") (pintype "bidirectional"))
    )
    (net (code "34") (name "Net-(U$32-P2)") (class "Default")
      (node (ref "U$31") (pin "OUT") (pinfunction "OUT_OUT") (pintype "bidirectional"))
      (node (ref "U$32") (pin "P$2") (pinfunction "P2_P$2") (pintype "bidirectional"))
    )
    (net (code "35") (name "Net-(U$33-D)") (class "Default")
      (node (ref "U$31") (pin "IN1") (pinfunction "IN1_IN1") (pintype "bidirectional"))
      (node (ref "U$33") (pin "3") (pinfunction "D_3") (pintype "bidirectional"))
    )
    (net (code "36") (name "Net-(U$33-G)") (class "Default")
      (node (ref "R7") (pin "1") (pinfunction "1_1") (pintype "passive"))
      (node (ref "U$33") (pin "1") (pinfunction "G_1") (pintype "bidirectional"))
      (node (ref "U$7") (pin "3") (pinfunction "D_3") (pintype "bidirectional"))
    )
    (net (code "37") (name "Net-(U1-ANT)") (class "Default")
      (node (ref "C3") (pin "1") (pinfunction "1_1") (pintype "passive"))
      (node (ref "L1") (pin "2") (pinfunction "2_2") (pintype "passive"))
      (node (ref "U1") (pin "30") (pinfunction "ANT_30") (pintype "bidirectional"))
    )
    (net (code "38") (name "Net-(U1-DCC)") (class "Default")
      (node (ref "L2") (pin "2") (pinfunction "2_2") (pintype "passive"))
      (node (ref "U1") (pin "47") (pinfunction "DCC_47") (pintype "bidirectional"))
    )
    (net (code "39") (name "Net-(U1-DEC1)") (class "Default")
      (node (ref "C4") (pin "1") (pinfunction "1_1") (pintype "passive"))
      (node (ref "U1") (pin "1") (pinfunction "DEC1_1") (pintype "bidirectional"))
    )
    (net (code "40") (name "Net-(U1-DEC2)") (class "Default")
      (node (ref "C6") (pin "1") (pinfunction "1_1") (pintype "passive"))
      (node (ref "U1") (pin "32") (pinfunction "DEC2_32") (pintype "bidirectional"))
    )
    (net (code "41") (name "Net-(U1-DEC3)") (class "Default")
      (node (ref "C7") (pin "1") (pinfunction "1_1") (pintype "passive"))
      (node (ref "U1") (pin "33") (pinfunction "DEC3_33") (pintype "bidirectional"))
    )
    (net (code "42") (name "Net-(U1-DEC4)") (class "Default")
      (node (ref "C10") (pin "1") (pinfunction "1_1") (pintype "passive"))
      (node (ref "L3") (pin "1") (pinfunction "1_1") (pintype "passive"))
      (node (ref "U1") (pin "46") (pinfunction "DEC4_46") (pintype "bidirectional"))
    )
    (net (code "43") (name "Net-(U1-P0_XL1)") (class "Default")
      (node (ref "C17") (pin "1") (pinfunction "1_1") (pintype "passive"))
      (node (ref "U1") (pin "2") (pinfunction "P0_XL1_2") (pintype "bidirectional"))
      (node (ref "X2") (pin "P$1") (pinfunction "P$1_P$1") (pintype "bidirectional"))
    )
    (net (code "44") (name "Net-(U1-P1_XL2)") (class "Default")
      (node (ref "C18") (pin "1") (pinfunction "1_1") (pintype "passive"))
      (node (ref "U1") (pin "3") (pinfunction "P1_XL2_3") (pintype "bidirectional"))
      (node (ref "X2") (pin "P$2") (pinfunction "P$2_P$2") (pintype "bidirectional"))
    )
    (net (code "45") (name "Net-(U1-P2_AIN0)") (class "Default")
      (node (ref "R8") (pin "1") (pinfunction "1_1") (pintype "passive"))
      (node (ref "U1") (pin "4") (pinfunction "P2_AIN0_4") (pintype "bidirectional"))
    )
    (net (code "46") (name "Net-(U1-P17)") (class "Default")
      (node (ref "R12") (pin "2") (pinfunction "2_2") (pintype "passive"))
      (node (ref "U1") (pin "20") (pinfunction "P17_20") (pintype "bidirectional"))
    )
    (net (code "47") (name "Net-(U1-XC1)") (class "Default")
      (node (ref "C1") (pin "1") (pinfunction "1_1") (pintype "passive"))
      (node (ref "U1") (pin "34") (pinfunction "XC1_34") (pintype "bidirectional"))
      (node (ref "X1") (pin "P3") (pinfunction "1_P3") (pintype "passive"))
    )
    (net (code "48") (name "Net-(U1-XC2)") (class "Default")
      (node (ref "C2") (pin "1") (pinfunction "1_1") (pintype "passive"))
      (node (ref "U1") (pin "35") (pinfunction "XC2_35") (pintype "bidirectional"))
      (node (ref "X1") (pin "P1") (pinfunction "2_P1") (pintype "passive"))
    )
    (net (code "49") (name "Net-(U2-CFG0)") (class "Default")
      (node (ref "U$6") (pin "OUT") (pinfunction "OUT_OUT") (pintype "bidirectional"))
      (node (ref "U2") (pin "6") (pinfunction "CFG0_6") (pintype "input"))
    )
    (net (code "50") (name "Net-(U2-CFG1)") (class "Default")
      (node (ref "U$5") (pin "OUT") (pinfunction "OUT_OUT") (pintype "bidirectional"))
      (node (ref "U2") (pin "5") (pinfunction "CFG1_5") (pintype "input"))
    )
    (net (code "51") (name "Net-(U2-CFG2)") (class "Default")
      (node (ref "U$4") (pin "OUT") (pinfunction "OUT_OUT") (pintype "bidirectional"))
      (node (ref "U2") (pin "4") (pinfunction "CFG2_4") (pintype "input"))
    )
    (net (code "52") (name "Net-(U2-ENHV)") (class "Default")
      (node (ref "U$2") (pin "OUT") (pinfunction "OUT_OUT") (pintype "bidirectional"))
      (node (ref "U2") (pin "12") (pinfunction "ENHV_12") (pintype "input"))
    )
    (net (code "53") (name "Net-(U2-ENLV)") (class "Default")
      (node (ref "U$3") (pin "OUT") (pinfunction "OUT_OUT") (pintype "bidirectional"))
      (node (ref "U2") (pin "18") (pinfunction "ENLV_18") (pintype "input"))
    )
    (net (code "54") (name "Net-(U2-FB_COLD)") (class "Default")
      (node (ref "R10") (pin "2") (pinfunction "2_2") (pintype "passive"))
      (node (ref "R9") (pin "1") (pinfunction "1_1") (pintype "passive"))
      (node (ref "U2") (pin "26") (pinfunction "FB_COLD_26") (pintype "bidirectional"))
    )
    (net (code "55") (name "Net-(U2-FB_HV)") (class "Default")
      (node (ref "R5") (pin "1") (pinfunction "1_1") (pintype "passive"))
      (node (ref "R6") (pin "1") (pinfunction "1_1") (pintype "passive"))
      (node (ref "U2") (pin "13") (pinfunction "FB_HV_13") (pintype "input"))
    )
    (net (code "56") (name "Net-(U2-PRIM)") (class "Default")
      (node (ref "U$12") (pin "P$1") (pinfunction "P$1_P$1") (pintype "bidirectional"))
      (node (ref "U2") (pin "17") (pinfunction "PRIM_17") (pintype "bidirectional"))
    )
    (net (code "57") (name "Net-(U2-SET_CHRDY)") (class "Default")
      (node (ref "R2") (pin "1") (pinfunction "1_1") (pintype "passive"))
      (node (ref "R3") (pin "2") (pinfunction "2_2") (pintype "passive"))
      (node (ref "U2") (pin "23") (pinfunction "SET_CHRDY_23") (pintype "bidirectional"))
    )
    (net (code "58") (name "Net-(U2-SET_OVCH)") (class "Default")
      (node (ref "R1") (pin "1") (pinfunction "1_1") (pintype "passive"))
      (node (ref "R2") (pin "2") (pinfunction "2_2") (pintype "passive"))
      (node (ref "U2") (pin "22") (pinfunction "SET_OVCH_22") (pintype "bidirectional"))
    )
    (net (code "59") (name "Net-(U2-SET_OVDIS)") (class "Default")
      (node (ref "R3") (pin "1") (pinfunction "1_1") (pintype "passive"))
      (node (ref "R4") (pin "2") (pinfunction "2_2") (pintype "passive"))
      (node (ref "U2") (pin "24") (pinfunction "SET_OVDIS_24") (pintype "bidirectional"))
    )
    (net (code "60") (name "Net-(U2-SRC)") (class "Default")
      (node (ref "R10") (pin "1") (pinfunction "1_1") (pintype "passive"))
      (node (ref "U$16") (pin "P$2") (pinfunction "VOUT_P$2") (pintype "bidirectional"))
      (node (ref "U$16") (pin "P$3") (pinfunction "VOUT_P$3") (pintype "bidirectional"))
      (node (ref "U$36") (pin "P$1") (pinfunction "P$1_P$1") (pintype "bidirectional"))
      (node (ref "U$39") (pin "P$1") (pinfunction "P$1_P$1") (pintype "bidirectional"))
      (node (ref "U2") (pin "25") (pinfunction "SRC_25") (pintype "input"))
    )
    (net (code "61") (name "Net-(U2-STATUS1)") (class "Default")
      (node (ref "U$14") (pin "P$1") (pinfunction "P$1_P$1") (pintype "bidirectional"))
      (node (ref "U2") (pin "20") (pinfunction "STATUS1_20") (pintype "output"))
    )
    (net (code "62") (name "Net-(U2-STATUS2)") (class "Default")
      (node (ref "U$13") (pin "P$1") (pinfunction "P$1_P$1") (pintype "bidirectional"))
      (node (ref "U2") (pin "19") (pinfunction "STATUS2_19") (pintype "output"))
    )
    (net (code "63") (name "Net-(U2-SWBUCK)") (class "Default")
      (node (ref "L5") (pin "2") (pinfunction "2_2") (pintype "passive"))
      (node (ref "U2") (pin "2") (pinfunction "SWBUCK_2") (pintype "bidirectional"))
    )
    (net (code "64") (name "unconnected-(U$10-P1-Pad1)") (class "Default")
      (node (ref "U$10") (pin "1") (pinfunction "P1_1") (pintype "bidirectional"))
    )
    (net (code "65") (name "unconnected-(U$10-P3-Pad3)") (class "Default")
      (node (ref "U$10") (pin "3") (pinfunction "P3_3") (pintype "bidirectional"))
    )
    (net (code "66") (name "unconnected-(U1-NC-Pad44)") (class "Default")
      (node (ref "U1") (pin "44") (pinfunction "NC_44") (pintype "bidirectional"))
    )
    (net (code "67") (name "unconnected-(U1-P19-Pad22)") (class "Default")
      (node (ref "U1") (pin "22") (pinfunction "P19_22") (pintype "bidirectional"))
    )
    (net (code "68") (name "unconnected-(U1-P20-Pad23)") (class "Default")
      (node (ref "U1") (pin "23") (pinfunction "P20_23") (pintype "bidirectional"))
    )
    (net (code "69") (name "unconnected-(U1-P22-Pad27)") (class "Default")
      (node (ref "U1") (pin "27") (pinfunction "P22_27") (pintype "bidirectional"))
    )
    (net (code "70") (name "unconnected-(U1-P23-Pad28)") (class "Default")
      (node (ref "U1") (pin "28") (pinfunction "P23_28") (pintype "bidirectional"))
    )
    (net (code "71") (name "unconnected-(U1-P24-Pad29)") (class "Default")
      (node (ref "U1") (pin "29") (pinfunction "P24_29") (pintype "bidirectional"))
    )
    (net (code "72") (name "unconnected-(U1-P25-Pad37)") (class "Default")
      (node (ref "U1") (pin "37") (pinfunction "P25_37") (pintype "bidirectional"))
    )
    (net (code "73") (name "unconnected-(U1-P26-Pad38)") (class "Default")
      (node (ref "U1") (pin "38") (pinfunction "P26_38") (pintype "bidirectional"))
    )
    (net (code "74") (name "unconnected-(U1-P27-Pad39)") (class "Default")
      (node (ref "U1") (pin "39") (pinfunction "P27_39") (pintype "bidirectional"))
    )
    (net (code "75") (name "unconnected-(U1-P28-Pad40)") (class "Default")
      (node (ref "U1") (pin "40") (pinfunction "P28_40") (pintype "bidirectional"))
    )
    (net (code "76") (name "unconnected-(U1-P29-Pad41)") (class "Default")
      (node (ref "U1") (pin "41") (pinfunction "P29_41") (pintype "bidirectional"))
    )
    (net (code "77") (name "unconnected-(U1-P30_AIN6-Pad42)") (class "Default")
      (node (ref "U1") (pin "42") (pinfunction "P30_AIN6_42") (pintype "bidirectional"))
    )
    (net (code "78") (name "unconnected-(U1-P31_AIN7-Pad43)") (class "Default")
      (node (ref "U1") (pin "43") (pinfunction "P31_AIN7_43") (pintype "bidirectional"))
    )
  )
)
